# untitled.net
KiCad netlist of a schematic drawn in EAGLE
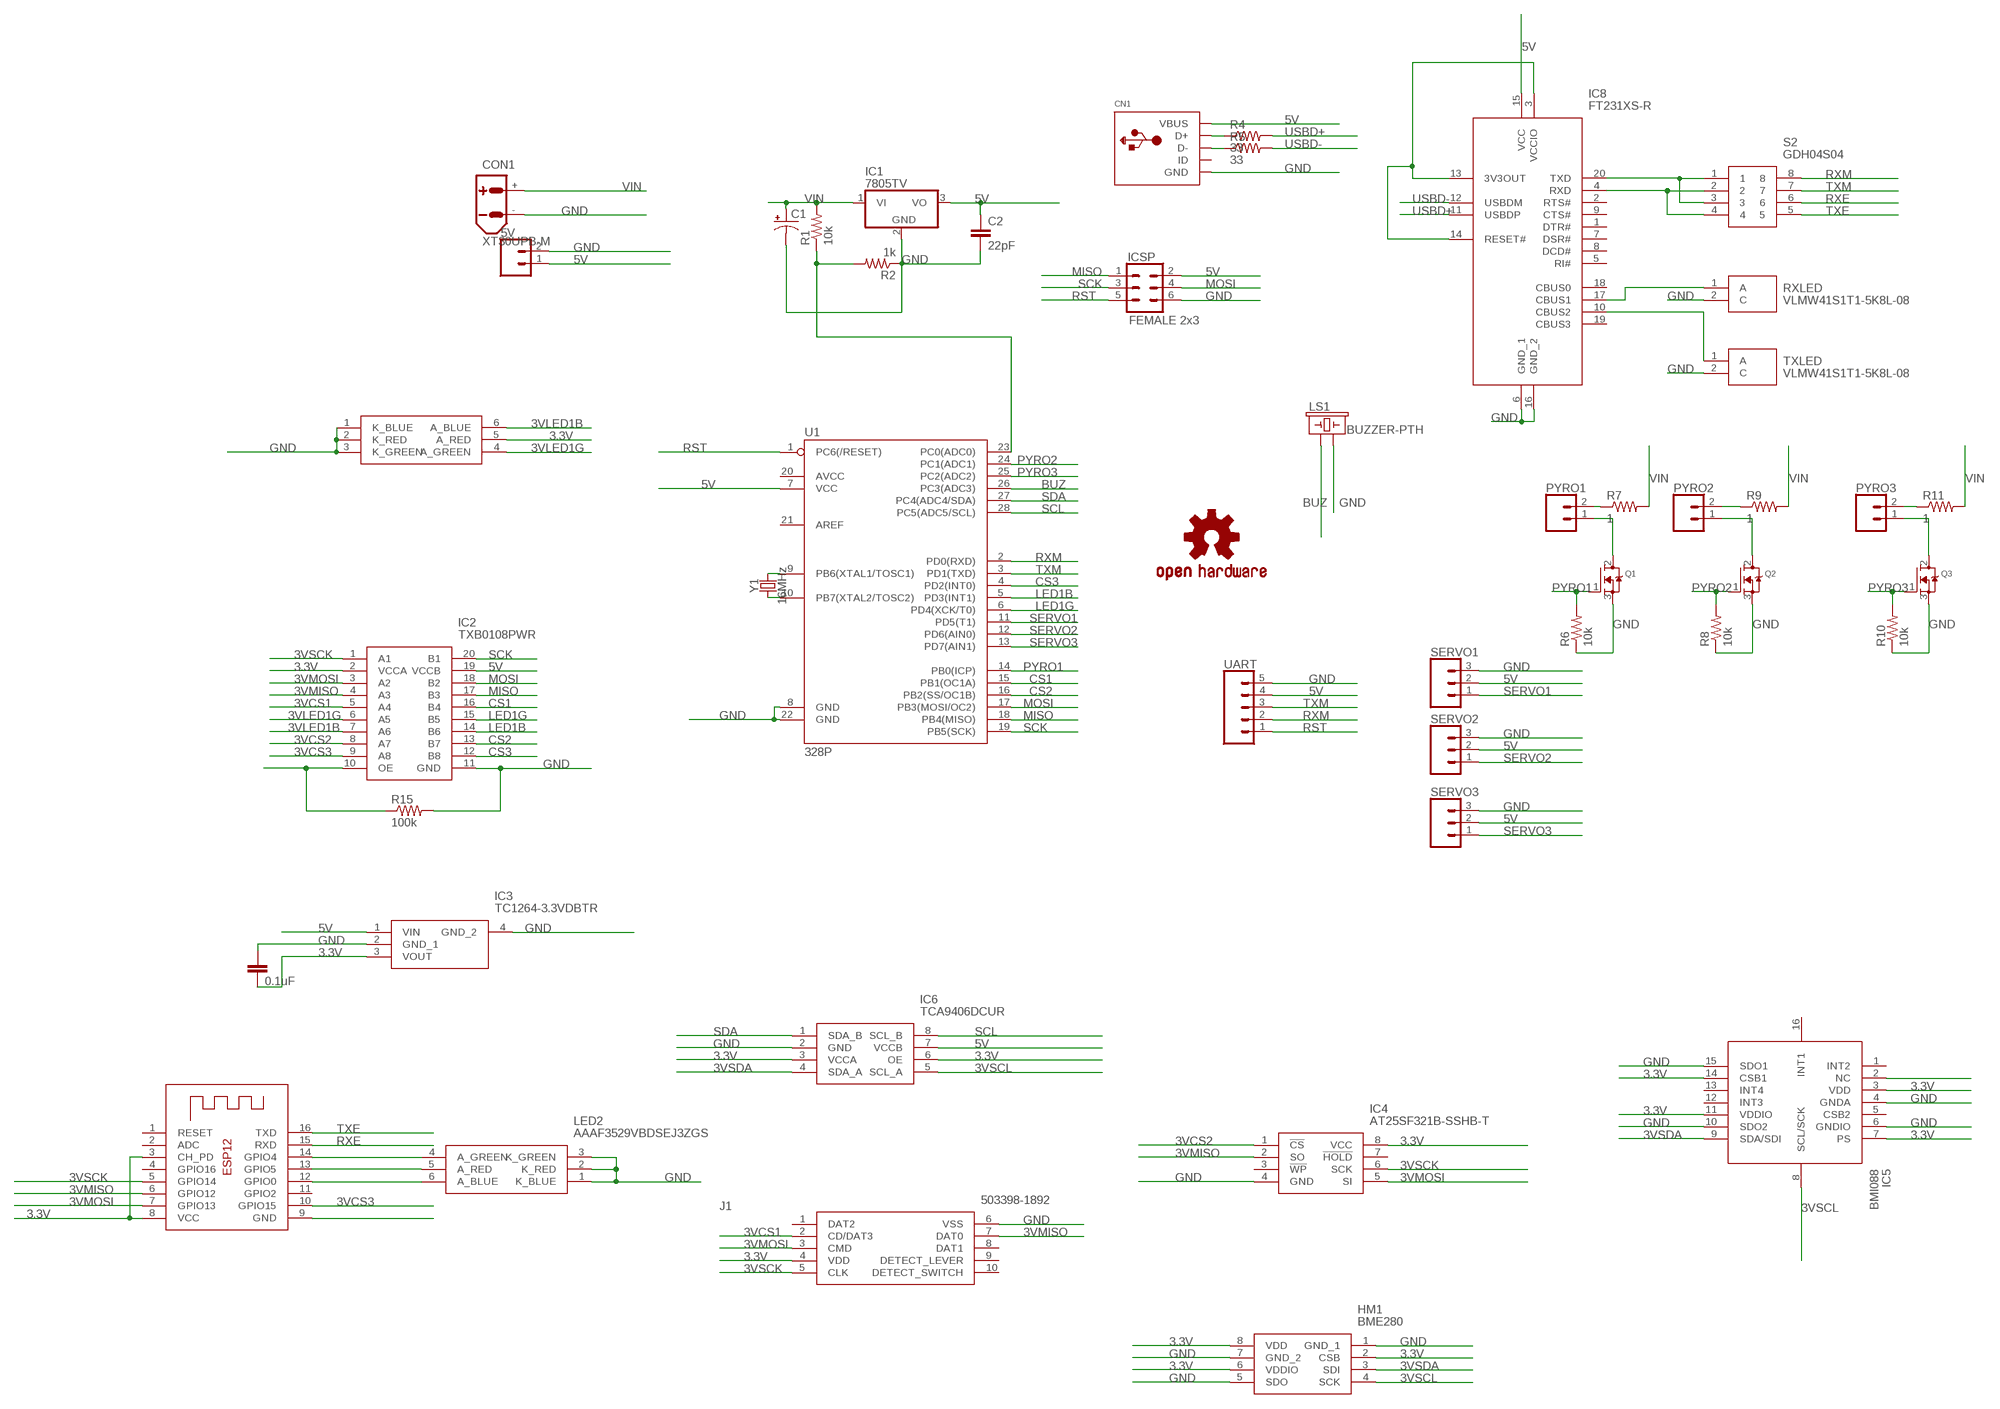
[diagram p0: schematic, sheet 1]

(export (version "E")
  (design (tool "Eeschema 10.0.6"))
  (components
    (comp (ref "5V")
      (value "CONN_02")
      (footprint "eagle-import:1X02")
      (libsource (lib "eagle-import") (part "CONN_02"))
    )
    (comp (ref "C1")
      (value "CPOL-USE3.5-8")
      (footprint "eagle-import:E3,5-8")
      (libsource (lib "eagle-import") (part "CPOL-USE3.5-8"))
    )
    (comp (ref "C2")
      (value "22pF")
      (footprint "eagle-import:CAP-PTH-2.54")
      (libsource (lib "eagle-import") (part "22PF-PTH-2.54MM-200V-5%"))
    )
    (comp (ref "C4")
      (value "0.1uF")
      (footprint "eagle-import:CAP-PTH-SMALL-KIT")
      (libsource (lib "eagle-import") (part "0.1UF-KIT-EZ-50V-20%"))
    )
    (comp (ref "CN1")
      (value "USBMINIB")
      (footprint "eagle-import:USB-MINIB")
      (libsource (lib "eagle-import") (part "USBMINIB"))
    )
    (comp (ref "CON1")
      (value "XT30UPB-M")
      (footprint "eagle-import:XT30UPB-M")
      (libsource (lib "eagle-import") (part "XT30UPB-M"))
    )
    (comp (ref "HM1")
      (value "BME280")
      (footprint "eagle-import:BME280")
      (fields (field (name "MOUSER_PART_NUMBER") "262-BME280"))
      (libsource (lib "eagle-import") (part "BME280"))
    )
    (comp (ref "IC1")
      (value "7805TV")
      (footprint "eagle-import:TO220V")
      (libsource (lib "eagle-import") (part "78TV05"))
    )
    (comp (ref "IC2")
      (value "TXB0108PWR")
      (footprint "eagle-import:SOP65P640X120-20N")
      (fields (field (name "MOUSER_PART_NUMBER") "595-TXB0108PWR"))
      (libsource (lib "eagle-import") (part "TXB0108PWR"))
    )
    (comp (ref "IC3")
      (value "TC1264-3.3VDBTR")
      (footprint "eagle-import:SOT230P700X180-4N")
      (fields (field (name "MOUSER_PART_NUMBER") "579-TC1264-3.3VDBTR"))
      (libsource (lib "eagle-import") (part "TC1264-3.3VDBTR"))
    )
    (comp (ref "IC4")
      (value "AT25SF321B-SSHB-T")
      (footprint "eagle-import:SOIC127P600X175-8N")
      (fields (field (name "MOUSER_PART_NUMBER") "988-AT25SF321BSSHB-T"))
      (libsource (lib "eagle-import") (part "AT25SF321B-SSHB-T"))
    )
    (comp (ref "IC5")
      (value "BMI088")
      (footprint "eagle-import:BMI088")
      (fields (field (name "MOUSER_PART_NUMBER") "262-BMI088"))
      (libsource (lib "eagle-import") (part "BMI088"))
    )
    (comp (ref "IC6")
      (value "TCA9406DCUR")
      (footprint "eagle-import:SOP50P310X90-8N")
      (fields (field (name "MOUSER_PART_NUMBER") "595-TCA9406DCUR"))
      (libsource (lib "eagle-import") (part "TCA9406DCUR"))
    )
    (comp (ref "IC8")
      (value "FT231XS-R")
      (footprint "eagle-import:SOP64P599X175-20N")
      (fields (field (name "MOUSER_PART_NUMBER") "895-FT231XS-R"))
      (libsource (lib "eagle-import") (part "FT231XS-R"))
    )
    (comp (ref "ICSP")
      (value "FEMALE 2x3")
      (footprint "eagle-import:2X3")
      (libsource (lib "eagle-import") (part "CONN_03X2FEMALE"))
    )
    (comp (ref "J1")
      (value "503398-1892")
      (footprint "eagle-import:503398-1892")
      (fields (field (name "MOUSER_PART_NUMBER") "538-503398-1892"))
      (libsource (lib "eagle-import") (part "503398-1892"))
    )
    (comp (ref "LED1")
      (value "AAAF3529VBDSEJ3ZGS")
      (footprint "eagle-import:AAAF3529VBDSEJ3ZGS")
      (fields (field (name "MOUSER_PART_NUMBER") "604-AAAF3529VBDSEJ3Z"))
      (libsource (lib "eagle-import") (part "AAAF3529VBDSEJ3ZGS"))
    )
    (comp (ref "LED2")
      (value "AAAF3529VBDSEJ3ZGS")
      (footprint "eagle-import:AAAF3529VBDSEJ3ZGS")
      (fields (field (name "MOUSER_PART_NUMBER") "604-AAAF3529VBDSEJ3Z"))
      (libsource (lib "eagle-import") (part "AAAF3529VBDSEJ3ZGS"))
    )
    (comp (ref "LOGO1")
      (value "OSHW-LOGOL")
      (footprint "eagle-import:OSHW-LOGO-L")
      (libsource (lib "eagle-import") (part "OSHW-LOGOL"))
    )
    (comp (ref "LS1")
      (value "BUZZER-PTH")
      (footprint "eagle-import:BUZZER-12MM")
      (libsource (lib "eagle-import") (part "BUZZER-PTH"))
    )
    (comp (ref "PYRO1")
      (value "CONN_025MM")
      (footprint "eagle-import:SCREWTERMINAL-5MM-2")
      (libsource (lib "eagle-import") (part "CONN_025MM"))
    )
    (comp (ref "PYRO2")
      (value "CONN_025MM")
      (footprint "eagle-import:SCREWTERMINAL-5MM-2")
      (libsource (lib "eagle-import") (part "CONN_025MM"))
    )
    (comp (ref "PYRO3")
      (value "CONN_025MM")
      (footprint "eagle-import:SCREWTERMINAL-5MM-2")
      (libsource (lib "eagle-import") (part "CONN_025MM"))
    )
    (comp (ref "Q1")
      (value "MOSFET-NGDS_TO220V")
      (footprint "eagle-import:TO220V")
      (libsource (lib "eagle-import") (part "MOSFET-NGDS_TO220V"))
    )
    (comp (ref "Q2")
      (value "MOSFET-NGDS_TO220V")
      (footprint "eagle-import:TO220V")
      (libsource (lib "eagle-import") (part "MOSFET-NGDS_TO220V"))
    )
    (comp (ref "Q3")
      (value "MOSFET-NGDS_TO220V")
      (footprint "eagle-import:TO220V")
      (libsource (lib "eagle-import") (part "MOSFET-NGDS_TO220V"))
    )
    (comp (ref "R1")
      (value "10k")
      (footprint "eagle-import:0805-THM")
      (libsource (lib "eagle-import") (part "adafruit_420_FLIPFLOP-RES"))
    )
    (comp (ref "R2")
      (value "1k")
      (footprint "eagle-import:0805-THM")
      (libsource (lib "eagle-import") (part "adafruit_420_FLIPFLOP-RES"))
    )
    (comp (ref "R4")
      (value "33")
      (footprint "eagle-import:0805-THM")
      (libsource (lib "eagle-import") (part "adafruit_420_FLIPFLOP-RES"))
    )
    (comp (ref "R5")
      (value "33")
      (footprint "eagle-import:0805-THM")
      (libsource (lib "eagle-import") (part "adafruit_420_FLIPFLOP-RES"))
    )
    (comp (ref "R6")
      (value "10k")
      (footprint "eagle-import:0805-THM")
      (libsource (lib "eagle-import") (part "FLIPFLOP-RES"))
    )
    (comp (ref "R7")
      (value "1")
      (footprint "eagle-import:0805-THM")
      (libsource (lib "eagle-import") (part "FLIPFLOP-RES"))
    )
    (comp (ref "R8")
      (value "10k")
      (footprint "eagle-import:0805-THM")
      (libsource (lib "eagle-import") (part "FLIPFLOP-RES"))
    )
    (comp (ref "R9")
      (value "1")
      (footprint "eagle-import:0805-THM")
      (libsource (lib "eagle-import") (part "FLIPFLOP-RES"))
    )
    (comp (ref "R10")
      (value "10k")
      (footprint "eagle-import:0805-THM")
      (libsource (lib "eagle-import") (part "FLIPFLOP-RES"))
    )
    (comp (ref "R11")
      (value "1")
      (footprint "eagle-import:0805-THM")
      (libsource (lib "eagle-import") (part "FLIPFLOP-RES"))
    )
    (comp (ref "R15")
      (value "100k")
      (footprint "eagle-import:0805-THM")
      (libsource (lib "eagle-import") (part "adafruit_420_FLIPFLOP-RES"))
    )
    (comp (ref "RXLED")
      (value "VLMW41S1T1-5K8L-08")
      (footprint "eagle-import:LEDM3528X185N")
      (fields (field (name "MOUSER_PART_NUMBER") "78-VLMW41S1T1"))
      (libsource (lib "eagle-import") (part "VLMW41S1T1-5K8L-08"))
    )
    (comp (ref "S2")
      (value "GDH04S04")
      (footprint "eagle-import:SOIC127P813X256-8N")
      (fields (field (name "MOUSER_PART_NUMBER") "506-GDH04S04"))
      (libsource (lib "eagle-import") (part "GDH04S04"))
    )
    (comp (ref "SERVO1")
      (value "CONN_03")
      (footprint "eagle-import:1X03")
      (libsource (lib "eagle-import") (part "CONN_03"))
    )
    (comp (ref "SERVO2")
      (value "CONN_03")
      (footprint "eagle-import:1X03")
      (libsource (lib "eagle-import") (part "CONN_03"))
    )
    (comp (ref "SERVO3")
      (value "CONN_03")
      (footprint "eagle-import:1X03")
      (libsource (lib "eagle-import") (part "CONN_03"))
    )
    (comp (ref "TXLED")
      (value "VLMW41S1T1-5K8L-08")
      (footprint "eagle-import:LEDM3528X185N")
      (fields (field (name "MOUSER_PART_NUMBER") "78-VLMW41S1T1"))
      (libsource (lib "eagle-import") (part "VLMW41S1T1-5K8L-08"))
    )
    (comp (ref "U1")
      (value "328P")
      (footprint "eagle-import:DIP28")
      (libsource (lib "eagle-import") (part "ATMEGA328P_PDIP"))
    )
    (comp (ref "UART")
      (value "CONN_05")
      (footprint "eagle-import:1X05")
      (libsource (lib "eagle-import") (part "CONN_05"))
    )
    (comp (ref "X1")
      (value "ESP-12")
      (footprint "eagle-import:ESP-12")
      (libsource (lib "eagle-import") (part "ESP-12"))
    )
    (comp (ref "Y1")
      (value "16MHz")
      (footprint "eagle-import:HC49US")
      (libsource (lib "eagle-import") (part "CRYSTAL-16MHZPTH-HC49US"))
    )
  )
  (nets
    (net (code "1") (name "/3.3V") (class "Default")
      (node (ref "C4") (pin "2") (pinfunction "2_2") (pintype "passive"))
      (node (ref "HM1") (pin "2") (pinfunction "CSB_2") (pintype "input"))
      (node (ref "HM1") (pin "6") (pinfunction "VDDIO_6") (pintype "power_in"))
      (node (ref "HM1") (pin "8") (pinfunction "VDD_8") (pintype "power_in"))
      (node (ref "IC2") (pin "2") (pinfunction "VCCA_2") (pintype "bidirectional"))
      (node (ref "IC3") (pin "3") (pinfunction "VOUT_3") (pintype "bidirectional"))
      (node (ref "IC4") (pin "8") (pinfunction "VCC_8") (pintype "power_in"))
      (node (ref "IC5") (pin "11") (pinfunction "VDDIO_11") (pintype "bidirectional"))
      (node (ref "IC5") (pin "14") (pinfunction "CSB1_14") (pintype "bidirectional"))
      (node (ref "IC5") (pin "3") (pinfunction "VDD_3") (pintype "bidirectional"))
      (node (ref "IC5") (pin "7") (pinfunction "PS_7") (pintype "bidirectional"))
      (node (ref "IC6") (pin "3") (pinfunction "VCCA_3") (pintype "bidirectional"))
      (node (ref "IC6") (pin "6") (pinfunction "OE_6") (pintype "bidirectional"))
      (node (ref "J1") (pin "4") (pinfunction "VDD_4") (pintype "bidirectional"))
      (node (ref "LED1") (pin "5") (pinfunction "A_RED_5") (pintype "bidirectional"))
      (node (ref "X1") (pin "3") (pinfunction "CH_PD_3") (pintype "input"))
      (node (ref "X1") (pin "8") (pinfunction "VCC_8") (pintype "power_in"))
    )
    (net (code "2") (name "/3VCS1") (class "Default")
      (node (ref "IC2") (pin "5") (pinfunction "A4_5") (pintype "bidirectional"))
      (node (ref "J1") (pin "2") (pinfunction "CD/DAT3_2") (pintype "bidirectional"))
    )
    (net (code "3") (name "/3VCS2") (class "Default")
      (node (ref "IC2") (pin "8") (pinfunction "A7_8") (pintype "bidirectional"))
      (node (ref "IC4") (pin "1") (pinfunction "~{CS}_1") (pintype "input"))
    )
    (net (code "4") (name "/3VCS3") (class "Default")
      (node (ref "IC2") (pin "9") (pinfunction "A8_9") (pintype "bidirectional"))
      (node (ref "X1") (pin "10") (pinfunction "GPIO15_10") (pintype "bidirectional"))
    )
    (net (code "5") (name "/3VLED1B") (class "Default")
      (node (ref "IC2") (pin "7") (pinfunction "A6_7") (pintype "bidirectional"))
      (node (ref "LED1") (pin "6") (pinfunction "A_BLUE_6") (pintype "bidirectional"))
    )
    (net (code "6") (name "/3VLED1G") (class "Default")
      (node (ref "IC2") (pin "6") (pinfunction "A5_6") (pintype "bidirectional"))
      (node (ref "LED1") (pin "4") (pinfunction "A_GREEN_4") (pintype "bidirectional"))
    )
    (net (code "7") (name "/3VMISO") (class "Default")
      (node (ref "IC2") (pin "4") (pinfunction "A3_4") (pintype "bidirectional"))
      (node (ref "IC4") (pin "2") (pinfunction "SO_2") (pintype "bidirectional"))
      (node (ref "J1") (pin "7") (pinfunction "DAT0_7") (pintype "bidirectional"))
      (node (ref "X1") (pin "6") (pinfunction "GPIO12_6") (pintype "bidirectional"))
    )
    (net (code "8") (name "/3VMOSI") (class "Default")
      (node (ref "IC2") (pin "3") (pinfunction "A2_3") (pintype "bidirectional"))
      (node (ref "IC4") (pin "5") (pinfunction "SI_5") (pintype "input"))
      (node (ref "J1") (pin "3") (pinfunction "CMD_3") (pintype "bidirectional"))
      (node (ref "X1") (pin "7") (pinfunction "GPIO13_7") (pintype "bidirectional"))
    )
    (net (code "9") (name "/3VSCK") (class "Default")
      (node (ref "IC2") (pin "1") (pinfunction "A1_1") (pintype "bidirectional"))
      (node (ref "IC4") (pin "6") (pinfunction "SCK_6") (pintype "input"))
      (node (ref "J1") (pin "5") (pinfunction "CLK_5") (pintype "bidirectional"))
      (node (ref "X1") (pin "5") (pinfunction "GPIO14_5") (pintype "bidirectional"))
    )
    (net (code "10") (name "/3VSCL") (class "Default")
      (node (ref "HM1") (pin "4") (pinfunction "SCK_4") (pintype "bidirectional"))
      (node (ref "IC5") (pin "8") (pinfunction "SCL/SCK_8") (pintype "bidirectional"))
      (node (ref "IC6") (pin "5") (pinfunction "SCL_A_5") (pintype "bidirectional"))
    )
    (net (code "11") (name "/3VSDA") (class "Default")
      (node (ref "HM1") (pin "3") (pinfunction "SDI_3") (pintype "bidirectional"))
      (node (ref "IC5") (pin "9") (pinfunction "SDA/SDI_9") (pintype "bidirectional"))
      (node (ref "IC6") (pin "4") (pinfunction "SDA_A_4") (pintype "bidirectional"))
    )
    (net (code "12") (name "/5V") (class "Default")
      (node (ref "5V") (pin "1") (pinfunction "1_1") (pintype "passive"))
      (node (ref "C2") (pin "1") (pinfunction "1_1") (pintype "passive"))
      (node (ref "CN1") (pin "VBUS") (pinfunction "VBUS_VBUS") (pintype "power_in"))
      (node (ref "IC1") (pin "3") (pinfunction "VO_3") (pintype "passive"))
      (node (ref "IC2") (pin "19") (pinfunction "VCCB_19") (pintype "bidirectional"))
      (node (ref "IC3") (pin "1") (pinfunction "VIN_1") (pintype "bidirectional"))
      (node (ref "IC6") (pin "7") (pinfunction "VCCB_7") (pintype "bidirectional"))
      (node (ref "IC8") (pin "15") (pinfunction "VCC_15") (pintype "bidirectional"))
      (node (ref "ICSP") (pin "2") (pinfunction "2_2") (pintype "bidirectional"))
      (node (ref "SERVO1") (pin "2") (pinfunction "2_2") (pintype "passive"))
      (node (ref "SERVO2") (pin "2") (pinfunction "2_2") (pintype "passive"))
      (node (ref "SERVO3") (pin "2") (pinfunction "2_2") (pintype "passive"))
      (node (ref "U1") (pin "7") (pinfunction "VCC_7") (pintype "bidirectional"))
      (node (ref "UART") (pin "4") (pinfunction "4_4") (pintype "passive"))
    )
    (net (code "13") (name "/BUZ") (class "Default")
      (node (ref "LS1") (pin "+") (pinfunction "1_+") (pintype "passive"))
      (node (ref "U1") (pin "26") (pinfunction "PC3(ADC3)_26") (pintype "bidirectional"))
    )
    (net (code "14") (name "/CS1") (class "Default")
      (node (ref "IC2") (pin "16") (pinfunction "B4_16") (pintype "bidirectional"))
      (node (ref "U1") (pin "15") (pinfunction "PB1(OC1A)_15") (pintype "bidirectional"))
    )
    (net (code "15") (name "/CS2") (class "Default")
      (node (ref "IC2") (pin "13") (pinfunction "B7_13") (pintype "bidirectional"))
      (node (ref "U1") (pin "16") (pinfunction "PB2(SS/OC1B)_16") (pintype "bidirectional"))
    )
    (net (code "16") (name "/CS3") (class "Default")
      (node (ref "IC2") (pin "12") (pinfunction "B8_12") (pintype "bidirectional"))
      (node (ref "U1") (pin "4") (pinfunction "PD2(INT0)_4") (pintype "bidirectional"))
    )
    (net (code "17") (name "/GND") (class "Default")
      (node (ref "5V") (pin "2") (pinfunction "2_2") (pintype "passive"))
      (node (ref "C1") (pin "-") (pinfunction "-_-") (pintype "passive"))
      (node (ref "C2") (pin "2") (pinfunction "2_2") (pintype "passive"))
      (node (ref "C4") (pin "1") (pinfunction "1_1") (pintype "passive"))
      (node (ref "CN1") (pin "GND") (pinfunction "GND_GND") (pintype "power_in"))
      (node (ref "CON1") (pin "-") (pinfunction "-_-") (pintype "power_in"))
      (node (ref "HM1") (pin "1") (pinfunction "GND_1_1") (pintype "power_in"))
      (node (ref "HM1") (pin "5") (pinfunction "SDO_5") (pintype "bidirectional"))
      (node (ref "HM1") (pin "7") (pinfunction "GND_2_7") (pintype "power_in"))
      (node (ref "IC1") (pin "2") (pinfunction "GND_2") (pintype "passive"))
      (node (ref "IC2") (pin "11") (pinfunction "GND_11") (pintype "bidirectional"))
      (node (ref "IC3") (pin "2") (pinfunction "GND_1_2") (pintype "bidirectional"))
      (node (ref "IC3") (pin "4") (pinfunction "GND_2_4") (pintype "bidirectional"))
      (node (ref "IC4") (pin "4") (pinfunction "GND_4") (pintype "power_in"))
      (node (ref "IC5") (pin "10") (pinfunction "SDO2_10") (pintype "bidirectional"))
      (node (ref "IC5") (pin "15") (pinfunction "SDO1_15") (pintype "bidirectional"))
      (node (ref "IC5") (pin "4") (pinfunction "GNDA_4") (pintype "bidirectional"))
      (node (ref "IC5") (pin "6") (pinfunction "GNDIO_6") (pintype "bidirectional"))
      (node (ref "IC6") (pin "2") (pinfunction "GND_2") (pintype "bidirectional"))
      (node (ref "IC8") (pin "16") (pinfunction "GND_2_16") (pintype "bidirectional"))
      (node (ref "IC8") (pin "6") (pinfunction "GND_1_6") (pintype "bidirectional"))
      (node (ref "ICSP") (pin "6") (pinfunction "6_6") (pintype "bidirectional"))
      (node (ref "J1") (pin "6") (pinfunction "VSS_6") (pintype "bidirectional"))
      (node (ref "LED1") (pin "1") (pinfunction "K_BLUE_1") (pintype "bidirectional"))
      (node (ref "LED1") (pin "2") (pinfunction "K_RED_2") (pintype "bidirectional"))
      (node (ref "LED1") (pin "3") (pinfunction "K_GREEN_3") (pintype "bidirectional"))
      (node (ref "LED2") (pin "1") (pinfunction "K_BLUE_1") (pintype "bidirectional"))
      (node (ref "LED2") (pin "2") (pinfunction "K_RED_2") (pintype "bidirectional"))
      (node (ref "LED2") (pin "3") (pinfunction "K_GREEN_3") (pintype "bidirectional"))
      (node (ref "LS1") (pin "-") (pinfunction "2_-") (pintype "passive"))
      (node (ref "Q1") (pin "3") (pinfunction "S_3") (pintype "bidirectional"))
      (node (ref "Q2") (pin "3") (pinfunction "S_3") (pintype "bidirectional"))
      (node (ref "Q3") (pin "3") (pinfunction "S_3") (pintype "bidirectional"))
      (node (ref "R10") (pin "1") (pinfunction "1_1") (pintype "passive"))
      (node (ref "R15") (pin "2") (pinfunction "2_2") (pintype "passive"))
      (node (ref "R2") (pin "1") (pinfunction "1_1") (pintype "passive"))
      (node (ref "R6") (pin "1") (pinfunction "1_1") (pintype "passive"))
      (node (ref "R8") (pin "1") (pinfunction "1_1") (pintype "passive"))
      (node (ref "RXLED") (pin "2") (pinfunction "C_2") (pintype "bidirectional"))
      (node (ref "SERVO1") (pin "3") (pinfunction "3_3") (pintype "passive"))
      (node (ref "SERVO2") (pin "3") (pinfunction "3_3") (pintype "passive"))
      (node (ref "SERVO3") (pin "3") (pinfunction "3_3") (pintype "passive"))
      (node (ref "TXLED") (pin "2") (pinfunction "C_2") (pintype "bidirectional"))
      (node (ref "U1") (pin "22") (pinfunction "GND_22") (pintype "bidirectional"))
      (node (ref "U1") (pin "8") (pinfunction "GND_8") (pintype "bidirectional"))
      (node (ref "UART") (pin "5") (pinfunction "5_5") (pintype "passive"))
      (node (ref "X1") (pin "9") (pinfunction "GND_9") (pintype "power_in"))
    )
    (net (code "18") (name "/LED1B") (class "Default")
      (node (ref "IC2") (pin "14") (pinfunction "B6_14") (pintype "bidirectional"))
      (node (ref "U1") (pin "5") (pinfunction "PD3(INT1)_5") (pintype "bidirectional"))
    )
    (net (code "19") (name "/LED1G") (class "Default")
      (node (ref "IC2") (pin "15") (pinfunction "B5_15") (pintype "bidirectional"))
      (node (ref "U1") (pin "6") (pinfunction "PD4(XCK/T0)_6") (pintype "bidirectional"))
    )
    (net (code "20") (name "/MISO") (class "Default")
      (node (ref "IC2") (pin "17") (pinfunction "B3_17") (pintype "bidirectional"))
      (node (ref "ICSP") (pin "1") (pinfunction "1_1") (pintype "bidirectional"))
      (node (ref "U1") (pin "18") (pinfunction "PB4(MISO)_18") (pintype "bidirectional"))
    )
    (net (code "21") (name "/MOSI") (class "Default")
      (node (ref "IC2") (pin "18") (pinfunction "B2_18") (pintype "bidirectional"))
      (node (ref "ICSP") (pin "4") (pinfunction "4_4") (pintype "bidirectional"))
      (node (ref "U1") (pin "17") (pinfunction "PB3(MOSI/OC2)_17") (pintype "bidirectional"))
    )
    (net (code "22") (name "/PYRO1") (class "Default")
      (node (ref "Q1") (pin "1") (pinfunction "G_1") (pintype "bidirectional"))
      (node (ref "R6") (pin "2") (pinfunction "2_2") (pintype "passive"))
      (node (ref "U1") (pin "14") (pinfunction "PB0(ICP)_14") (pintype "bidirectional"))
    )
    (net (code "23") (name "/PYRO2") (class "Default")
      (node (ref "Q2") (pin "1") (pinfunction "G_1") (pintype "bidirectional"))
      (node (ref "R8") (pin "2") (pinfunction "2_2") (pintype "passive"))
      (node (ref "U1") (pin "24") (pinfunction "PC1(ADC1)_24") (pintype "bidirectional"))
    )
    (net (code "24") (name "/PYRO3") (class "Default")
      (node (ref "Q3") (pin "1") (pinfunction "G_1") (pintype "bidirectional"))
      (node (ref "R10") (pin "2") (pinfunction "2_2") (pintype "passive"))
      (node (ref "U1") (pin "25") (pinfunction "PC2(ADC2)_25") (pintype "bidirectional"))
    )
    (net (code "25") (name "/RST") (class "Default")
      (node (ref "ICSP") (pin "5") (pinfunction "5_5") (pintype "bidirectional"))
      (node (ref "U1") (pin "1") (pinfunction "PC6(/RESET)_1") (pintype "bidirectional"))
      (node (ref "UART") (pin "1") (pinfunction "1_1") (pintype "passive"))
    )
    (net (code "26") (name "/RXE") (class "Default")
      (node (ref "S2") (pin "6") (pinfunction "6_6") (pintype "bidirectional"))
      (node (ref "X1") (pin "15") (pinfunction "RXD_15") (pintype "input"))
    )
    (net (code "27") (name "/RXM") (class "Default")
      (node (ref "S2") (pin "8") (pinfunction "8_8") (pintype "bidirectional"))
      (node (ref "U1") (pin "2") (pinfunction "PD0(RXD)_2") (pintype "bidirectional"))
      (node (ref "UART") (pin "2") (pinfunction "2_2") (pintype "passive"))
    )
    (net (code "28") (name "/SCK") (class "Default")
      (node (ref "IC2") (pin "20") (pinfunction "B1_20") (pintype "bidirectional"))
      (node (ref "ICSP") (pin "3") (pinfunction "3_3") (pintype "bidirectional"))
      (node (ref "U1") (pin "19") (pinfunction "PB5(SCK)_19") (pintype "bidirectional"))
    )
    (net (code "29") (name "/SCL") (class "Default")
      (node (ref "IC6") (pin "8") (pinfunction "SCL_B_8") (pintype "bidirectional"))
      (node (ref "U1") (pin "28") (pinfunction "PC5(ADC5/SCL)_28") (pintype "bidirectional"))
    )
    (net (code "30") (name "/SDA") (class "Default")
      (node (ref "IC6") (pin "1") (pinfunction "SDA_B_1") (pintype "bidirectional"))
      (node (ref "U1") (pin "27") (pinfunction "PC4(ADC4/SDA)_27") (pintype "bidirectional"))
    )
    (net (code "31") (name "/SERVO1") (class "Default")
      (node (ref "SERVO1") (pin "1") (pinfunction "1_1") (pintype "passive"))
      (node (ref "U1") (pin "11") (pinfunction "PD5(T1)_11") (pintype "bidirectional"))
    )
    (net (code "32") (name "/SERVO2") (class "Default")
      (node (ref "SERVO2") (pin "1") (pinfunction "1_1") (pintype "passive"))
      (node (ref "U1") (pin "12") (pinfunction "PD6(AIN0)_12") (pintype "bidirectional"))
    )
    (net (code "33") (name "/SERVO3") (class "Default")
      (node (ref "SERVO3") (pin "1") (pinfunction "1_1") (pintype "passive"))
      (node (ref "U1") (pin "13") (pinfunction "PD7(AIN1)_13") (pintype "bidirectional"))
    )
    (net (code "34") (name "/TXE") (class "Default")
      (node (ref "S2") (pin "5") (pinfunction "5_5") (pintype "bidirectional"))
      (node (ref "X1") (pin "16") (pinfunction "TXD_16") (pintype "output"))
    )
    (net (code "35") (name "/TXM") (class "Default")
      (node (ref "S2") (pin "7") (pinfunction "7_7") (pintype "bidirectional"))
      (node (ref "U1") (pin "3") (pinfunction "PD1(TXD)_3") (pintype "bidirectional"))
      (node (ref "UART") (pin "3") (pinfunction "3_3") (pintype "passive"))
    )
    (net (code "36") (name "/USBD+") (class "Default")
      (node (ref "IC8") (pin "11") (pinfunction "USBDP_11") (pintype "bidirectional"))
      (node (ref "R4") (pin "2") (pinfunction "2_2") (pintype "passive"))
    )
    (net (code "37") (name "/USBD-") (class "Default")
      (node (ref "IC8") (pin "12") (pinfunction "USBDM_12") (pintype "bidirectional"))
      (node (ref "R5") (pin "2") (pinfunction "2_2") (pintype "passive"))
    )
    (net (code "38") (name "/VIN") (class "Default")
      (node (ref "C1") (pin "+") (pinfunction "+_+") (pintype "passive"))
      (node (ref "CON1") (pin "+") (pinfunction "+_+") (pintype "power_in"))
      (node (ref "IC1") (pin "1") (pinfunction "VI_1") (pintype "input"))
      (node (ref "R1") (pin "2") (pinfunction "2_2") (pintype "passive"))
      (node (ref "R11") (pin "2") (pinfunction "2_2") (pintype "passive"))
      (node (ref "R7") (pin "2") (pinfunction "2_2") (pintype "passive"))
      (node (ref "R9") (pin "2") (pinfunction "2_2") (pintype "passive"))
    )
    (net (code "39") (name "Net-(CN1-PadD+)") (class "Default")
      (node (ref "CN1") (pin "D+") (pinfunction "D+_D+") (pintype "bidirectional"))
      (node (ref "R4") (pin "1") (pinfunction "1_1") (pintype "passive"))
    )
    (net (code "40") (name "Net-(CN1-PadD-)") (class "Default")
      (node (ref "CN1") (pin "D-") (pinfunction "D-_D-") (pintype "bidirectional"))
      (node (ref "R5") (pin "1") (pinfunction "1_1") (pintype "passive"))
    )
    (net (code "41") (name "Net-(IC2-OE)") (class "Default")
      (node (ref "IC2") (pin "10") (pinfunction "OE_10") (pintype "bidirectional"))
      (node (ref "R15") (pin "1") (pinfunction "1_1") (pintype "passive"))
    )
    (net (code "42") (name "Net-(IC8-3V3OUT)") (class "Default")
      (node (ref "IC8") (pin "13") (pinfunction "3V3OUT_13") (pintype "bidirectional"))
      (node (ref "IC8") (pin "14") (pinfunction "RESET#_14") (pintype "bidirectional"))
      (node (ref "IC8") (pin "3") (pinfunction "VCCIO_3") (pintype "bidirectional"))
    )
    (net (code "43") (name "Net-(IC8-CBUS1)") (class "Default")
      (node (ref "IC8") (pin "17") (pinfunction "CBUS1_17") (pintype "bidirectional"))
      (node (ref "RXLED") (pin "1") (pinfunction "A_1") (pintype "bidirectional"))
    )
    (net (code "44") (name "Net-(IC8-CBUS2)") (class "Default")
      (node (ref "IC8") (pin "10") (pinfunction "CBUS2_10") (pintype "bidirectional"))
      (node (ref "TXLED") (pin "1") (pinfunction "A_1") (pintype "bidirectional"))
    )
    (net (code "45") (name "Net-(IC8-RXD)") (class "Default")
      (node (ref "IC8") (pin "4") (pinfunction "RXD_4") (pintype "bidirectional"))
      (node (ref "S2") (pin "2") (pinfunction "2_2") (pintype "bidirectional"))
      (node (ref "S2") (pin "4") (pinfunction "4_4") (pintype "bidirectional"))
    )
    (net (code "46") (name "Net-(IC8-TXD)") (class "Default")
      (node (ref "IC8") (pin "20") (pinfunction "TXD_20") (pintype "bidirectional"))
      (node (ref "S2") (pin "1") (pinfunction "1_1") (pintype "bidirectional"))
      (node (ref "S2") (pin "3") (pinfunction "3_3") (pintype "bidirectional"))
    )
    (net (code "47") (name "Net-(LED2-A_BLUE)") (class "Default")
      (node (ref "LED2") (pin "6") (pinfunction "A_BLUE_6") (pintype "bidirectional"))
      (node (ref "X1") (pin "12") (pinfunction "GPIO0_12") (pintype "bidirectional"))
    )
    (net (code "48") (name "Net-(LED2-A_GREEN)") (class "Default")
      (node (ref "LED2") (pin "4") (pinfunction "A_GREEN_4") (pintype "bidirectional"))
      (node (ref "X1") (pin "14") (pinfunction "GPIO4_14") (pintype "bidirectional"))
    )
    (net (code "49") (name "Net-(LED2-A_RED)") (class "Default")
      (node (ref "LED2") (pin "5") (pinfunction "A_RED_5") (pintype "bidirectional"))
      (node (ref "X1") (pin "13") (pinfunction "GPIO5_13") (pintype "bidirectional"))
    )
    (net (code "50") (name "Net-(PYRO1-Pad2)") (class "Default")
      (node (ref "PYRO1") (pin "2") (pinfunction "2_2") (pintype "passive"))
      (node (ref "R7") (pin "1") (pinfunction "1_1") (pintype "passive"))
    )
    (net (code "51") (name "Net-(PYRO2-Pad2)") (class "Default")
      (node (ref "PYRO2") (pin "2") (pinfunction "2_2") (pintype "passive"))
      (node (ref "R9") (pin "1") (pinfunction "1_1") (pintype "passive"))
    )
    (net (code "52") (name "Net-(PYRO3-Pad2)") (class "Default")
      (node (ref "PYRO3") (pin "2") (pinfunction "2_2") (pintype "passive"))
      (node (ref "R11") (pin "1") (pinfunction "1_1") (pintype "passive"))
    )
    (net (code "53") (name "Net-(Q1-D)") (class "Default")
      (node (ref "PYRO1") (pin "1") (pinfunction "1_1") (pintype "passive"))
      (node (ref "Q1") (pin "2") (pinfunction "D_2") (pintype "bidirectional"))
    )
    (net (code "54") (name "Net-(Q2-D)") (class "Default")
      (node (ref "PYRO2") (pin "1") (pinfunction "1_1") (pintype "passive"))
      (node (ref "Q2") (pin "2") (pinfunction "D_2") (pintype "bidirectional"))
    )
    (net (code "55") (name "Net-(Q3-D)") (class "Default")
      (node (ref "PYRO3") (pin "1") (pinfunction "1_1") (pintype "passive"))
      (node (ref "Q3") (pin "2") (pinfunction "D_2") (pintype "bidirectional"))
    )
    (net (code "56") (name "Net-(U1-PB6(XTAL1{slash}TOSC1))") (class "Default")
      (node (ref "U1") (pin "9") (pinfunction "PB6(XTAL1/TOSC1)_9") (pintype "bidirectional"))
      (node (ref "Y1") (pin "2") (pinfunction "2_2") (pintype "passive"))
    )
    (net (code "57") (name "Net-(U1-PB7(XTAL2{slash}TOSC2))") (class "Default")
      (node (ref "U1") (pin "10") (pinfunction "PB7(XTAL2/TOSC2)_10") (pintype "bidirectional"))
      (node (ref "Y1") (pin "1") (pinfunction "1_1") (pintype "passive"))
    )
    (net (code "58") (name "Net-(U1-PC0(ADC0))") (class "Default")
      (node (ref "R1") (pin "1") (pinfunction "1_1") (pintype "passive"))
      (node (ref "R2") (pin "2") (pinfunction "2_2") (pintype "passive"))
      (node (ref "U1") (pin "23") (pinfunction "PC0(ADC0)_23") (pintype "bidirectional"))
    )
    (net (code "59") (name "unconnected-(CN1-PadID)") (class "Default")
      (node (ref "CN1") (pin "ID") (pinfunction "ID_ID") (pintype "bidirectional"))
    )
    (net (code "60") (name "unconnected-(IC4-~{HOLD}-Pad7)") (class "Default")
      (node (ref "IC4") (pin "7") (pinfunction "~{HOLD}_7") (pintype "input"))
    )
    (net (code "61") (name "unconnected-(IC4-~{WP}-Pad3)") (class "Default")
      (node (ref "IC4") (pin "3") (pinfunction "~{WP}_3") (pintype "input"))
    )
    (net (code "62") (name "unconnected-(IC5-CSB2-Pad5)") (class "Default")
      (node (ref "IC5") (pin "5") (pinfunction "CSB2_5") (pintype "bidirectional"))
    )
    (net (code "63") (name "unconnected-(IC5-INT1-Pad16)") (class "Default")
      (node (ref "IC5") (pin "16") (pinfunction "INT1_16") (pintype "bidirectional"))
    )
    (net (code "64") (name "unconnected-(IC5-INT2-Pad1)") (class "Default")
      (node (ref "IC5") (pin "1") (pinfunction "INT2_1") (pintype "bidirectional"))
    )
    (net (code "65") (name "unconnected-(IC5-INT3-Pad12)") (class "Default")
      (node (ref "IC5") (pin "12") (pinfunction "INT3_12") (pintype "bidirectional"))
    )
    (net (code "66") (name "unconnected-(IC5-INT4-Pad13)") (class "Default")
      (node (ref "IC5") (pin "13") (pinfunction "INT4_13") (pintype "bidirectional"))
    )
    (net (code "67") (name "unconnected-(IC5-NC-Pad2)") (class "Default")
      (node (ref "IC5") (pin "2") (pinfunction "NC_2") (pintype "no_connect"))
    )
    (net (code "68") (name "unconnected-(IC8-CBUS0-Pad18)") (class "Default")
      (node (ref "IC8") (pin "18") (pinfunction "CBUS0_18") (pintype "bidirectional"))
    )
    (net (code "69") (name "unconnected-(IC8-CBUS3-Pad19)") (class "Default")
      (node (ref "IC8") (pin "19") (pinfunction "CBUS3_19") (pintype "bidirectional"))
    )
    (net (code "70") (name "unconnected-(IC8-CTS#-Pad9)") (class "Default")
      (node (ref "IC8") (pin "9") (pinfunction "CTS#_9") (pintype "bidirectional"))
    )
    (net (code "71") (name "unconnected-(IC8-DCD#-Pad8)") (class "Default")
      (node (ref "IC8") (pin "8") (pinfunction "DCD#_8") (pintype "bidirectional"))
    )
    (net (code "72") (name "unconnected-(IC8-DSR#-Pad7)") (class "Default")
      (node (ref "IC8") (pin "7") (pinfunction "DSR#_7") (pintype "bidirectional"))
    )
    (net (code "73") (name "unconnected-(IC8-DTR#-Pad1)") (class "Default")
      (node (ref "IC8") (pin "1") (pinfunction "DTR#_1") (pintype "bidirectional"))
    )
    (net (code "74") (name "unconnected-(IC8-RI#-Pad5)") (class "Default")
      (node (ref "IC8") (pin "5") (pinfunction "RI#_5") (pintype "bidirectional"))
    )
    (net (code "75") (name "unconnected-(IC8-RTS#-Pad2)") (class "Default")
      (node (ref "IC8") (pin "2") (pinfunction "RTS#_2") (pintype "bidirectional"))
    )
    (net (code "76") (name "unconnected-(J1-DAT1-Pad8)") (class "Default")
      (node (ref "J1") (pin "8") (pinfunction "DAT1_8") (pintype "bidirectional"))
    )
    (net (code "77") (name "unconnected-(J1-DAT2-Pad1)") (class "Default")
      (node (ref "J1") (pin "1") (pinfunction "DAT2_1") (pintype "bidirectional"))
    )
    (net (code "78") (name "unconnected-(J1-DETECT_LEVER-Pad9)") (class "Default")
      (node (ref "J1") (pin "9") (pinfunction "DETECT_LEVER_9") (pintype "bidirectional"))
    )
    (net (code "79") (name "unconnected-(J1-DETECT_SWITCH-Pad10)") (class "Default")
      (node (ref "J1") (pin "10") (pinfunction "DETECT_SWITCH_10") (pintype "bidirectional"))
    )
    (net (code "80") (name "unconnected-(U1-AREF-Pad21)") (class "Default")
      (node (ref "U1") (pin "21") (pinfunction "AREF_21") (pintype "bidirectional"))
    )
    (net (code "81") (name "unconnected-(U1-AVCC-Pad20)") (class "Default")
      (node (ref "U1") (pin "20") (pinfunction "AVCC_20") (pintype "bidirectional"))
    )
    (net (code "82") (name "unconnected-(X1-ADC-Pad2)") (class "Default")
      (node (ref "X1") (pin "2") (pinfunction "ADC_2") (pintype "passive"))
    )
    (net (code "83") (name "unconnected-(X1-GPIO2-Pad11)") (class "Default")
      (node (ref "X1") (pin "11") (pinfunction "GPIO2_11") (pintype "bidirectional"))
    )
    (net (code "84") (name "unconnected-(X1-GPIO16-Pad4)") (class "Default")
      (node (ref "X1") (pin "4") (pinfunction "GPIO16_4") (pintype "bidirectional"))
    )
    (net (code "85") (name "unconnected-(X1-RESET-Pad1)") (class "Default")
      (node (ref "X1") (pin "1") (pinfunction "RESET_1") (pintype "input"))
    )
  )
)
